# ARDUINO_GPIO.net
KiCad netlist of a schematic drawn in Altium Designer
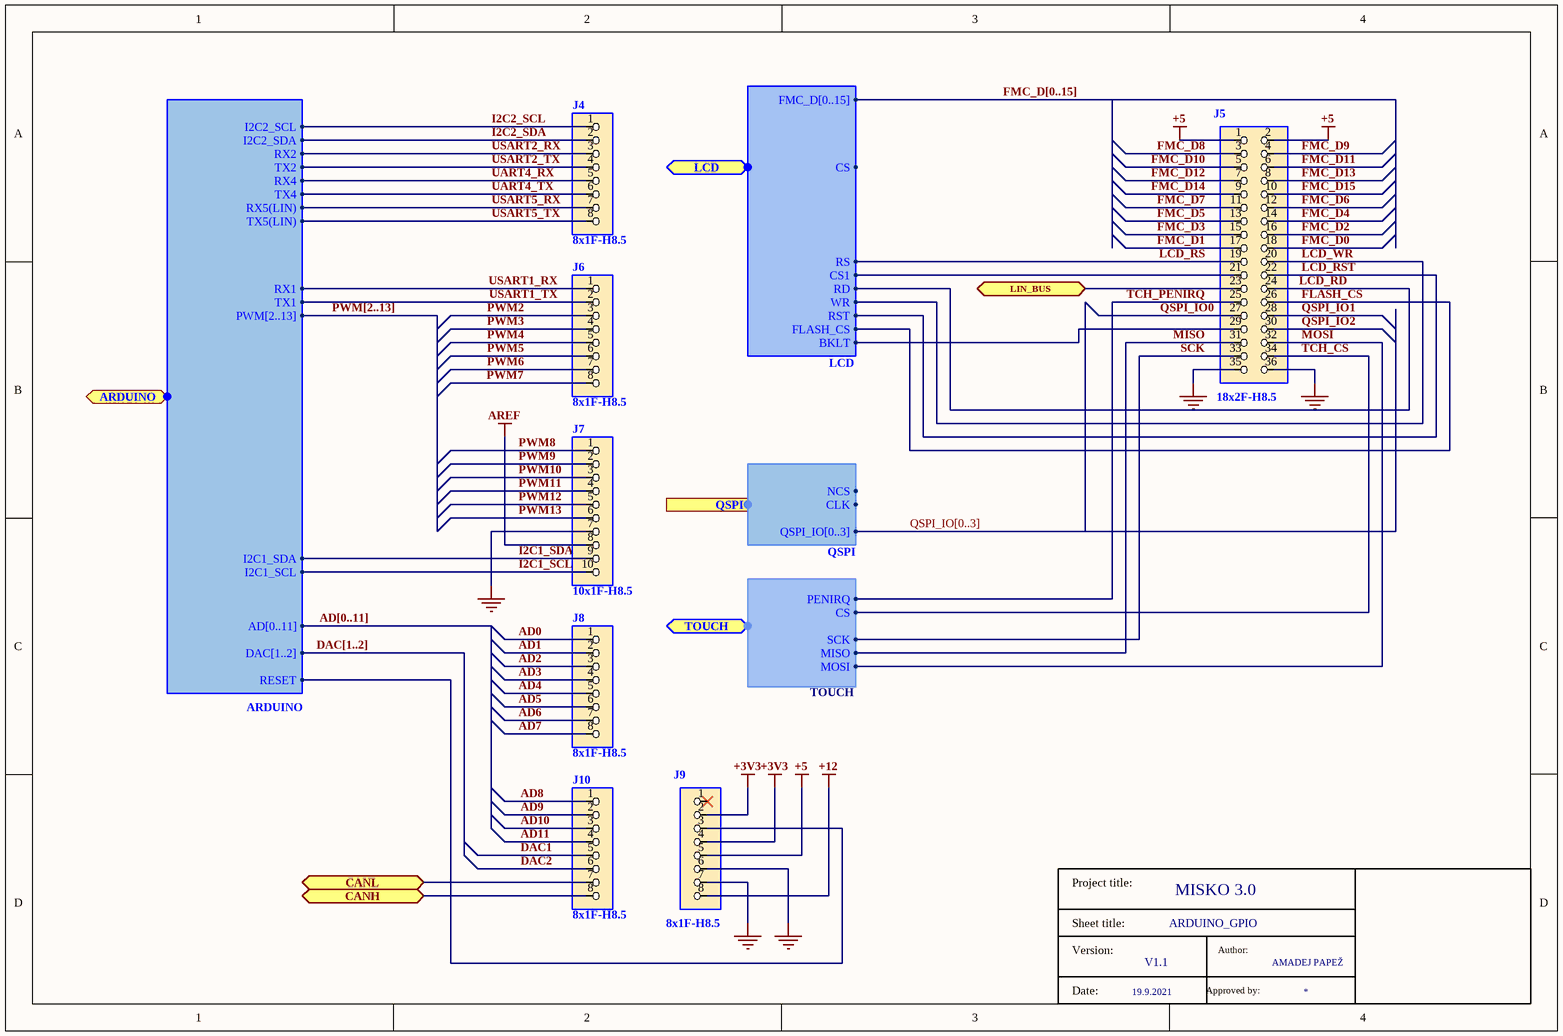
[diagram p0: ARDUINO_GPIO.SchDoc]

(export (version "E")
  (design (tool "Eeschema 10.0.6"))
  (components
    (comp (ref "J4")
      (value "8x1F-H8.5")
      (footprint "1X08")
      (description "PINHD-1X8")
      (libsource (lib "MISKO3_V6") (part "PINHD-1X8"))
    )
    (comp (ref "J5")
      (value "18x2F-H8.5")
      (footprint "2X18")
      (description "PINHD-2X18")
      (libsource (lib "MISKO3_V6") (part "PINHD-2X18"))
    )
    (comp (ref "J6")
      (value "8x1F-H8.5")
      (footprint "1X08")
      (description "PINHD-1X8")
      (libsource (lib "MISKO3_V6") (part "PINHD-1X8"))
    )
    (comp (ref "J7")
      (value "10x1F-H8.5")
      (footprint "1X10")
      (description "PINHD-1X10")
      (libsource (lib "MISKO3_V6") (part "PINHD-1X10"))
    )
    (comp (ref "J8")
      (value "8x1F-H8.5")
      (footprint "1X08")
      (description "PINHD-1X8")
      (libsource (lib "MISKO3_V6") (part "PINHD-1X8"))
    )
    (comp (ref "J9")
      (value "8x1F-H8.5")
      (footprint "1X08")
      (description "PINHD-1X8")
      (libsource (lib "") (part "PINHD-1X8_1"))
    )
    (comp (ref "J10")
      (value "8x1F-H8.5")
      (footprint "1X08")
      (description "PINHD-1X8")
      (libsource (lib "MISKO3_V6") (part "PINHD-1X8"))
    )
    (comp (ref "T6") (value "~") (libsource (lib "MISKO3_V6") (part "Title block")))
  )
  (nets
    (net (code "5") (name "+3V3") (class "Default")
      (node (ref "J9") (pin "2") (pinfunction "2_2") (pintype "passive"))
      (node (ref "J9") (pin "4") (pinfunction "4_4") (pintype "passive"))
    )
    (net (code "6") (name "+5") (class "Default")
      (node (ref "J5") (pin "1") (pinfunction "1_1") (pintype "passive"))
      (node (ref "J5") (pin "2") (pinfunction "2_2") (pintype "passive"))
      (node (ref "J9") (pin "5") (pinfunction "5_5") (pintype "passive"))
    )
    (net (code "7") (name "+12") (class "Default")
      (node (ref "J9") (pin "8") (pinfunction "8_8") (pintype "passive"))
    )
    (net (code "8") (name "/AD0") (class "Default")
      (node (ref "J8") (pin "1") (pinfunction "1_1") (pintype "passive"))
    )
    (net (code "9") (name "/AD1") (class "Default")
      (node (ref "J8") (pin "2") (pinfunction "2_2") (pintype "passive"))
    )
    (net (code "10") (name "/AD2") (class "Default")
      (node (ref "J8") (pin "3") (pinfunction "3_3") (pintype "passive"))
    )
    (net (code "11") (name "/AD3") (class "Default")
      (node (ref "J8") (pin "4") (pinfunction "4_4") (pintype "passive"))
    )
    (net (code "12") (name "/AD4") (class "Default")
      (node (ref "J8") (pin "5") (pinfunction "5_5") (pintype "passive"))
    )
    (net (code "13") (name "/AD5") (class "Default")
      (node (ref "J8") (pin "6") (pinfunction "6_6") (pintype "passive"))
    )
    (net (code "14") (name "/AD6") (class "Default")
      (node (ref "J8") (pin "7") (pinfunction "7_7") (pintype "passive"))
    )
    (net (code "15") (name "/AD7") (class "Default")
      (node (ref "J8") (pin "8") (pinfunction "8_8") (pintype "passive"))
    )
    (net (code "16") (name "/AD8") (class "Default")
      (node (ref "J10") (pin "1") (pinfunction "1_1") (pintype "passive"))
    )
    (net (code "17") (name "/AD9") (class "Default")
      (node (ref "J10") (pin "2") (pinfunction "2_2") (pintype "passive"))
    )
    (net (code "18") (name "/AD10") (class "Default")
      (node (ref "J10") (pin "3") (pinfunction "3_3") (pintype "passive"))
    )
    (net (code "19") (name "/AD11") (class "Default")
      (node (ref "J10") (pin "4") (pinfunction "4_4") (pintype "passive"))
    )
    (net (code "21") (name "/BKLT") (class "Default")
      (node (ref "J5") (pin "29") (pinfunction "29_29") (pintype "passive"))
    )
    (net (code "22") (name "/CANH") (class "Default")
      (node (ref "J10") (pin "8") (pinfunction "8_8") (pintype "passive"))
    )
    (net (code "23") (name "/CANL") (class "Default")
      (node (ref "J10") (pin "7") (pinfunction "7_7") (pintype "passive"))
    )
    (net (code "24") (name "/CS1") (class "Default")
      (node (ref "J5") (pin "21") (pinfunction "21_21") (pintype "passive"))
    )
    (net (code "25") (name "/DAC1") (class "Default")
      (node (ref "J10") (pin "5") (pinfunction "5_5") (pintype "passive"))
    )
    (net (code "26") (name "/DAC2") (class "Default")
      (node (ref "J10") (pin "6") (pinfunction "6_6") (pintype "passive"))
    )
    (net (code "28") (name "/FLASH_CS") (class "Default")
      (node (ref "J5") (pin "26") (pinfunction "26_26") (pintype "passive"))
    )
    (net (code "29") (name "/FMC_D0") (class "Default")
      (node (ref "J5") (pin "18") (pinfunction "18_18") (pintype "passive"))
    )
    (net (code "30") (name "/FMC_D1") (class "Default")
      (node (ref "J5") (pin "17") (pinfunction "17_17") (pintype "passive"))
    )
    (net (code "31") (name "/FMC_D2") (class "Default")
      (node (ref "J5") (pin "16") (pinfunction "16_16") (pintype "passive"))
    )
    (net (code "32") (name "/FMC_D3") (class "Default")
      (node (ref "J5") (pin "15") (pinfunction "15_15") (pintype "passive"))
    )
    (net (code "33") (name "/FMC_D4") (class "Default")
      (node (ref "J5") (pin "14") (pinfunction "14_14") (pintype "passive"))
    )
    (net (code "34") (name "/FMC_D5") (class "Default")
      (node (ref "J5") (pin "13") (pinfunction "13_13") (pintype "passive"))
    )
    (net (code "35") (name "/FMC_D6") (class "Default")
      (node (ref "J5") (pin "12") (pinfunction "12_12") (pintype "passive"))
    )
    (net (code "36") (name "/FMC_D7") (class "Default")
      (node (ref "J5") (pin "11") (pinfunction "11_11") (pintype "passive"))
    )
    (net (code "37") (name "/FMC_D8") (class "Default")
      (node (ref "J5") (pin "3") (pinfunction "3_3") (pintype "passive"))
    )
    (net (code "38") (name "/FMC_D9") (class "Default")
      (node (ref "J5") (pin "4") (pinfunction "4_4") (pintype "passive"))
    )
    (net (code "39") (name "/FMC_D10") (class "Default")
      (node (ref "J5") (pin "5") (pinfunction "5_5") (pintype "passive"))
    )
    (net (code "40") (name "/FMC_D11") (class "Default")
      (node (ref "J5") (pin "6") (pinfunction "6_6") (pintype "passive"))
    )
    (net (code "41") (name "/FMC_D12") (class "Default")
      (node (ref "J5") (pin "7") (pinfunction "7_7") (pintype "passive"))
    )
    (net (code "42") (name "/FMC_D13") (class "Default")
      (node (ref "J5") (pin "8") (pinfunction "8_8") (pintype "passive"))
    )
    (net (code "43") (name "/FMC_D14") (class "Default")
      (node (ref "J5") (pin "9") (pinfunction "9_9") (pintype "passive"))
    )
    (net (code "44") (name "/FMC_D15") (class "Default")
      (node (ref "J5") (pin "10") (pinfunction "10_10") (pintype "passive"))
    )
    (net (code "45") (name "/I2C1_SCL") (class "Default")
      (node (ref "J7") (pin "10") (pinfunction "10_10") (pintype "passive"))
    )
    (net (code "46") (name "/I2C1_SDA") (class "Default")
      (node (ref "J7") (pin "9") (pinfunction "9_9") (pintype "passive"))
    )
    (net (code "47") (name "/I2C2_SCL") (class "Default")
      (node (ref "J4") (pin "1") (pinfunction "1_1") (pintype "passive"))
    )
    (net (code "48") (name "/I2C2_SDA") (class "Default")
      (node (ref "J4") (pin "2") (pinfunction "2_2") (pintype "passive"))
    )
    (net (code "49") (name "/LCD_RD") (class "Default")
      (node (ref "J5") (pin "24") (pinfunction "24_24") (pintype "passive"))
    )
    (net (code "50") (name "/LCD_RS") (class "Default")
      (node (ref "J5") (pin "19") (pinfunction "19_19") (pintype "passive"))
    )
    (net (code "51") (name "/LCD_RST") (class "Default")
      (node (ref "J5") (pin "22") (pinfunction "22_22") (pintype "passive"))
    )
    (net (code "52") (name "/LCD_WR") (class "Default")
      (node (ref "J5") (pin "20") (pinfunction "20_20") (pintype "passive"))
    )
    (net (code "54") (name "/LIN_BUS") (class "Default")
      (node (ref "J5") (pin "23") (pinfunction "23_23") (pintype "passive"))
    )
    (net (code "55") (name "/MISO") (class "Default")
      (node (ref "J5") (pin "31") (pinfunction "31_31") (pintype "passive"))
    )
    (net (code "56") (name "/MOSI") (class "Default")
      (node (ref "J5") (pin "32") (pinfunction "32_32") (pintype "passive"))
    )
    (net (code "57") (name "/PWM2") (class "Default")
      (node (ref "J6") (pin "3") (pinfunction "3_3") (pintype "passive"))
    )
    (net (code "58") (name "/PWM3") (class "Default")
      (node (ref "J6") (pin "4") (pinfunction "4_4") (pintype "passive"))
    )
    (net (code "59") (name "/PWM4") (class "Default")
      (node (ref "J6") (pin "5") (pinfunction "5_5") (pintype "passive"))
    )
    (net (code "60") (name "/PWM5") (class "Default")
      (node (ref "J6") (pin "6") (pinfunction "6_6") (pintype "passive"))
    )
    (net (code "61") (name "/PWM6") (class "Default")
      (node (ref "J6") (pin "7") (pinfunction "7_7") (pintype "passive"))
    )
    (net (code "62") (name "/PWM7") (class "Default")
      (node (ref "J6") (pin "8") (pinfunction "8_8") (pintype "passive"))
    )
    (net (code "63") (name "/PWM8") (class "Default")
      (node (ref "J7") (pin "1") (pinfunction "1_1") (pintype "passive"))
    )
    (net (code "64") (name "/PWM9") (class "Default")
      (node (ref "J7") (pin "2") (pinfunction "2_2") (pintype "passive"))
    )
    (net (code "65") (name "/PWM10") (class "Default")
      (node (ref "J7") (pin "3") (pinfunction "3_3") (pintype "passive"))
    )
    (net (code "66") (name "/PWM11") (class "Default")
      (node (ref "J7") (pin "4") (pinfunction "4_4") (pintype "passive"))
    )
    (net (code "67") (name "/PWM12") (class "Default")
      (node (ref "J7") (pin "5") (pinfunction "5_5") (pintype "passive"))
    )
    (net (code "68") (name "/PWM13") (class "Default")
      (node (ref "J7") (pin "6") (pinfunction "6_6") (pintype "passive"))
    )
    (net (code "70") (name "/QSPI_IO0") (class "Default")
      (node (ref "J5") (pin "27") (pinfunction "27_27") (pintype "passive"))
    )
    (net (code "71") (name "/QSPI_IO1") (class "Default")
      (node (ref "J5") (pin "28") (pinfunction "28_28") (pintype "passive"))
    )
    (net (code "72") (name "/QSPI_IO2") (class "Default")
      (node (ref "J5") (pin "30") (pinfunction "30_30") (pintype "passive"))
    )
    (net (code "74") (name "/RESET") (class "Default")
      (node (ref "J9") (pin "3") (pinfunction "3_3") (pintype "passive"))
    )
    (net (code "75") (name "/SCK") (class "Default")
      (node (ref "J5") (pin "33") (pinfunction "33_33") (pintype "passive"))
    )
    (net (code "76") (name "/TCH_CS") (class "Default")
      (node (ref "J5") (pin "34") (pinfunction "34_34") (pintype "passive"))
    )
    (net (code "77") (name "/TCH_PENIRQ") (class "Default")
      (node (ref "J5") (pin "25") (pinfunction "25_25") (pintype "passive"))
    )
    (net (code "78") (name "/UART4_RX") (class "Default")
      (node (ref "J4") (pin "5") (pinfunction "5_5") (pintype "passive"))
    )
    (net (code "79") (name "/UART4_TX") (class "Default")
      (node (ref "J4") (pin "6") (pinfunction "6_6") (pintype "passive"))
    )
    (net (code "80") (name "/USART1_RX") (class "Default")
      (node (ref "J6") (pin "1") (pinfunction "1_1") (pintype "passive"))
    )
    (net (code "81") (name "/USART1_TX") (class "Default")
      (node (ref "J6") (pin "2") (pinfunction "2_2") (pintype "passive"))
    )
    (net (code "82") (name "/USART2_RX") (class "Default")
      (node (ref "J4") (pin "3") (pinfunction "3_3") (pintype "passive"))
    )
    (net (code "83") (name "/USART2_TX") (class "Default")
      (node (ref "J4") (pin "4") (pinfunction "4_4") (pintype "passive"))
    )
    (net (code "84") (name "/USART5_RX") (class "Default")
      (node (ref "J4") (pin "7") (pinfunction "7_7") (pintype "passive"))
    )
    (net (code "85") (name "/USART5_TX") (class "Default")
      (node (ref "J4") (pin "8") (pinfunction "8_8") (pintype "passive"))
    )
    (net (code "90") (name "AREF") (class "Default")
      (node (ref "J7") (pin "8") (pinfunction "8_8") (pintype "passive"))
    )
    (net (code "91") (name "GND") (class "Default")
      (node (ref "J5") (pin "35") (pinfunction "35_35") (pintype "passive"))
      (node (ref "J5") (pin "36") (pinfunction "36_36") (pintype "passive"))
      (node (ref "J7") (pin "7") (pinfunction "7_7") (pintype "passive"))
      (node (ref "J9") (pin "6") (pinfunction "6_6") (pintype "passive"))
      (node (ref "J9") (pin "7") (pinfunction "7_7") (pintype "passive"))
    )
    (net (code "92") (name "unconnected-(J9-Pad1)") (class "Default")
      (node (ref "J9") (pin "1") (pinfunction "1_1") (pintype "passive+no_connect"))
    )
  )
)
